# statuspanel.net
KiCad netlist of a schematic drawn in EAGLE
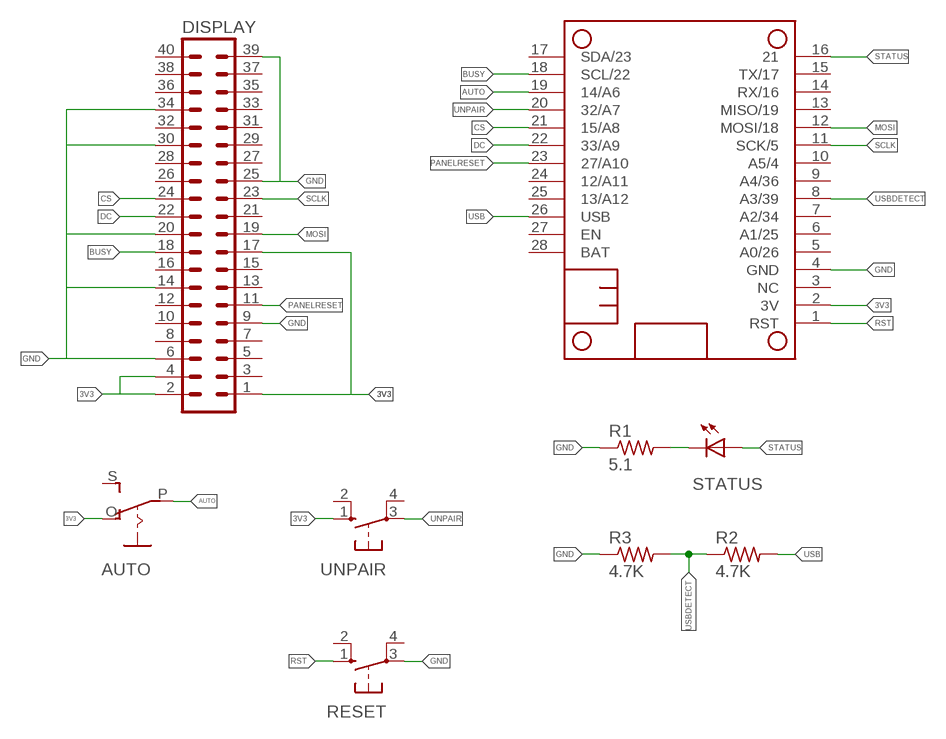
[diagram p0: schematic, sheet 1]

(export (version "E")
  (design (tool "Eeschema 10.0.6"))
  (components
    (comp (ref "AUTO")
      (value "EG1218S")
      (footprint "eagle-import:EG1218")
      (libsource (lib "eagle-import") (part "EG1218S"))
    )
    (comp (ref "DISPLAY")
      (value "MA20-2")
      (footprint "eagle-import:MA20-2")
      (libsource (lib "eagle-import") (part "MA20-2"))
    )
    (comp (ref "HUZZAH32")
      (value "HUZZAH32_NODIM")
      (footprint "eagle-import:FEATHERWING_DIM")
      (libsource (lib "eagle-import") (part "HUZZAH32_NODIM"))
    )
    (comp (ref "R1")
      (value "5.1")
      (footprint "eagle-import:R0805")
      (libsource (lib "eagle-import") (part "R-US_R0805"))
    )
    (comp (ref "R2")
      (value "4.7K")
      (footprint "eagle-import:R0805")
      (libsource (lib "eagle-import") (part "R-US_R0805"))
    )
    (comp (ref "R3")
      (value "4.7K")
      (footprint "eagle-import:R0805")
      (libsource (lib "eagle-import") (part "R-US_R0805"))
    )
    (comp (ref "RESET")
      (value "10-XX")
      (footprint "eagle-import:B3F-10XX")
      (fields (field (name "MPN") "B3F-1000"))
      (libsource (lib "eagle-import") (part "10-XX"))
    )
    (comp (ref "STATUS")
      (value "LED3MM")
      (footprint "eagle-import:LED3MM")
      (libsource (lib "eagle-import") (part "LED3MM"))
    )
    (comp (ref "UNPAIR")
      (value "10-XX")
      (footprint "eagle-import:B3F-10XX")
      (fields (field (name "MPN") "B3F-1000"))
      (libsource (lib "eagle-import") (part "10-XX"))
    )
  )
  (nets
    (net (code "1") (name "/BAT") (class "Default")
      (node (ref "HUZZAH32") (pin "28") (pinfunction "BAT_28") (pintype "power_in"))
    )
    (net (code "2") (name "3V3") (class "Default")
      (node (ref "AUTO") (pin "O") (pinfunction "O_O") (pintype "passive"))
      (node (ref "DISPLAY") (pin "1") (pinfunction "1_1") (pintype "passive"))
      (node (ref "DISPLAY") (pin "17") (pinfunction "17_17") (pintype "passive"))
      (node (ref "DISPLAY") (pin "2") (pinfunction "2_2") (pintype "passive"))
      (node (ref "DISPLAY") (pin "4") (pinfunction "4_4") (pintype "passive"))
      (node (ref "HUZZAH32") (pin "2") (pinfunction "3V_2") (pintype "power_in"))
      (node (ref "UNPAIR") (pin "1") (pinfunction "S_1") (pintype "passive"))
    )
    (net (code "3") (name "AUTO") (class "Default")
      (node (ref "AUTO") (pin "P") (pinfunction "P_P") (pintype "passive"))
      (node (ref "HUZZAH32") (pin "19") (pinfunction "14/A6_19") (pintype "bidirectional"))
    )
    (net (code "4") (name "BUSY") (class "Default")
      (node (ref "DISPLAY") (pin "18") (pinfunction "18_18") (pintype "passive"))
      (node (ref "HUZZAH32") (pin "18") (pinfunction "SCL/22_18") (pintype "bidirectional"))
    )
    (net (code "5") (name "CS") (class "Default")
      (node (ref "DISPLAY") (pin "24") (pinfunction "24_24") (pintype "passive"))
      (node (ref "HUZZAH32") (pin "21") (pinfunction "15/A8_21") (pintype "bidirectional"))
    )
    (net (code "6") (name "DC") (class "Default")
      (node (ref "DISPLAY") (pin "22") (pinfunction "22_22") (pintype "passive"))
      (node (ref "HUZZAH32") (pin "22") (pinfunction "33/A9_22") (pintype "bidirectional"))
    )
    (net (code "7") (name "GND") (class "Default")
      (node (ref "DISPLAY") (pin "14") (pinfunction "14_14") (pintype "passive"))
      (node (ref "DISPLAY") (pin "20") (pinfunction "20_20") (pintype "passive"))
      (node (ref "DISPLAY") (pin "25") (pinfunction "25_25") (pintype "passive"))
      (node (ref "DISPLAY") (pin "30") (pinfunction "30_30") (pintype "passive"))
      (node (ref "DISPLAY") (pin "34") (pinfunction "34_34") (pintype "passive"))
      (node (ref "DISPLAY") (pin "39") (pinfunction "39_39") (pintype "passive"))
      (node (ref "DISPLAY") (pin "6") (pinfunction "6_6") (pintype "passive"))
      (node (ref "DISPLAY") (pin "9") (pinfunction "9_9") (pintype "passive"))
      (node (ref "HUZZAH32") (pin "4") (pinfunction "GND_4") (pintype "power_in"))
      (node (ref "R1") (pin "1") (pinfunction "1_1") (pintype "passive"))
      (node (ref "R3") (pin "1") (pinfunction "1_1") (pintype "passive"))
      (node (ref "RESET") (pin "3") (pinfunction "P_3") (pintype "passive"))
    )
    (net (code "8") (name "MOSI") (class "Default")
      (node (ref "DISPLAY") (pin "19") (pinfunction "19_19") (pintype "passive"))
      (node (ref "HUZZAH32") (pin "12") (pinfunction "MOSI/18_12") (pintype "bidirectional"))
    )
    (net (code "9") (name "Net-(STATUS-C)") (class "Default")
      (node (ref "R1") (pin "2") (pinfunction "2_2") (pintype "passive"))
      (node (ref "STATUS") (pin "K") (pinfunction "C_K") (pintype "passive"))
    )
    (net (code "10") (name "PANELRESET") (class "Default")
      (node (ref "DISPLAY") (pin "11") (pinfunction "11_11") (pintype "passive"))
      (node (ref "HUZZAH32") (pin "23") (pinfunction "27/A10_23") (pintype "bidirectional"))
    )
    (net (code "11") (name "RST") (class "Default")
      (node (ref "HUZZAH32") (pin "1") (pinfunction "RST_1") (pintype "input"))
      (node (ref "RESET") (pin "1") (pinfunction "S_1") (pintype "passive"))
    )
    (net (code "12") (name "SCLK") (class "Default")
      (node (ref "DISPLAY") (pin "23") (pinfunction "23_23") (pintype "passive"))
      (node (ref "HUZZAH32") (pin "11") (pinfunction "SCK/5_11") (pintype "bidirectional"))
    )
    (net (code "13") (name "STATUS") (class "Default")
      (node (ref "HUZZAH32") (pin "16") (pinfunction "21_16") (pintype "bidirectional"))
      (node (ref "STATUS") (pin "A") (pinfunction "A_A") (pintype "passive"))
    )
    (net (code "14") (name "UNPAIR") (class "Default")
      (node (ref "HUZZAH32") (pin "20") (pinfunction "32/A7_20") (pintype "bidirectional"))
      (node (ref "UNPAIR") (pin "3") (pinfunction "P_3") (pintype "passive"))
    )
    (net (code "15") (name "USB") (class "Default")
      (node (ref "HUZZAH32") (pin "26") (pinfunction "USB_26") (pintype "power_in"))
      (node (ref "R2") (pin "2") (pinfunction "2_2") (pintype "passive"))
    )
    (net (code "16") (name "USBDETECT") (class "Default")
      (node (ref "HUZZAH32") (pin "8") (pinfunction "A3/39_8") (pintype "bidirectional"))
      (node (ref "R2") (pin "1") (pinfunction "1_1") (pintype "passive"))
      (node (ref "R3") (pin "2") (pinfunction "2_2") (pintype "passive"))
    )
    (net (code "17") (name "unconnected-(AUTO-PadS)") (class "Default")
      (node (ref "AUTO") (pin "S") (pinfunction "S_S") (pintype "passive"))
    )
    (net (code "18") (name "unconnected-(DISPLAY-Pad3)") (class "Default")
      (node (ref "DISPLAY") (pin "3") (pinfunction "3_3") (pintype "passive"))
    )
    (net (code "19") (name "unconnected-(DISPLAY-Pad5)") (class "Default")
      (node (ref "DISPLAY") (pin "5") (pinfunction "5_5") (pintype "passive"))
    )
    (net (code "20") (name "unconnected-(DISPLAY-Pad7)") (class "Default")
      (node (ref "DISPLAY") (pin "7") (pinfunction "7_7") (pintype "passive"))
    )
    (net (code "21") (name "unconnected-(DISPLAY-Pad8)") (class "Default")
      (node (ref "DISPLAY") (pin "8") (pinfunction "8_8") (pintype "passive"))
    )
    (net (code "22") (name "unconnected-(DISPLAY-Pad10)") (class "Default")
      (node (ref "DISPLAY") (pin "10") (pinfunction "10_10") (pintype "passive"))
    )
    (net (code "23") (name "unconnected-(DISPLAY-Pad12)") (class "Default")
      (node (ref "DISPLAY") (pin "12") (pinfunction "12_12") (pintype "passive"))
    )
    (net (code "24") (name "unconnected-(DISPLAY-Pad13)") (class "Default")
      (node (ref "DISPLAY") (pin "13") (pinfunction "13_13") (pintype "passive"))
    )
    (net (code "25") (name "unconnected-(DISPLAY-Pad15)") (class "Default")
      (node (ref "DISPLAY") (pin "15") (pinfunction "15_15") (pintype "passive"))
    )
    (net (code "26") (name "unconnected-(DISPLAY-Pad16)") (class "Default")
      (node (ref "DISPLAY") (pin "16") (pinfunction "16_16") (pintype "passive"))
    )
    (net (code "27") (name "unconnected-(DISPLAY-Pad21)") (class "Default")
      (node (ref "DISPLAY") (pin "21") (pinfunction "21_21") (pintype "passive"))
    )
    (net (code "28") (name "unconnected-(DISPLAY-Pad26)") (class "Default")
      (node (ref "DISPLAY") (pin "26") (pinfunction "26_26") (pintype "passive"))
    )
    (net (code "29") (name "unconnected-(DISPLAY-Pad27)") (class "Default")
      (node (ref "DISPLAY") (pin "27") (pinfunction "27_27") (pintype "passive"))
    )
    (net (code "30") (name "unconnected-(DISPLAY-Pad28)") (class "Default")
      (node (ref "DISPLAY") (pin "28") (pinfunction "28_28") (pintype "passive"))
    )
    (net (code "31") (name "unconnected-(DISPLAY-Pad29)") (class "Default")
      (node (ref "DISPLAY") (pin "29") (pinfunction "29_29") (pintype "passive"))
    )
    (net (code "32") (name "unconnected-(DISPLAY-Pad31)") (class "Default")
      (node (ref "DISPLAY") (pin "31") (pinfunction "31_31") (pintype "passive"))
    )
    (net (code "33") (name "unconnected-(DISPLAY-Pad32)") (class "Default")
      (node (ref "DISPLAY") (pin "32") (pinfunction "32_32") (pintype "passive"))
    )
    (net (code "34") (name "unconnected-(DISPLAY-Pad33)") (class "Default")
      (node (ref "DISPLAY") (pin "33") (pinfunction "33_33") (pintype "passive"))
    )
    (net (code "35") (name "unconnected-(DISPLAY-Pad35)") (class "Default")
      (node (ref "DISPLAY") (pin "35") (pinfunction "35_35") (pintype "passive"))
    )
    (net (code "36") (name "unconnected-(DISPLAY-Pad36)") (class "Default")
      (node (ref "DISPLAY") (pin "36") (pinfunction "36_36") (pintype "passive"))
    )
    (net (code "37") (name "unconnected-(DISPLAY-Pad37)") (class "Default")
      (node (ref "DISPLAY") (pin "37") (pinfunction "37_37") (pintype "passive"))
    )
    (net (code "38") (name "unconnected-(DISPLAY-Pad38)") (class "Default")
      (node (ref "DISPLAY") (pin "38") (pinfunction "38_38") (pintype "passive"))
    )
    (net (code "39") (name "unconnected-(DISPLAY-Pad40)") (class "Default")
      (node (ref "DISPLAY") (pin "40") (pinfunction "40_40") (pintype "passive"))
    )
    (net (code "40") (name "unconnected-(HUZZAH32-12{slash}A11-Pad24)") (class "Default")
      (node (ref "HUZZAH32") (pin "24") (pinfunction "12/A11_24") (pintype "bidirectional"))
    )
    (net (code "41") (name "unconnected-(HUZZAH32-13{slash}A12-Pad25)") (class "Default")
      (node (ref "HUZZAH32") (pin "25") (pinfunction "13/A12_25") (pintype "bidirectional"))
    )
    (net (code "42") (name "unconnected-(HUZZAH32-A0{slash}26-Pad5)") (class "Default")
      (node (ref "HUZZAH32") (pin "5") (pinfunction "A0/26_5") (pintype "bidirectional"))
    )
    (net (code "43") (name "unconnected-(HUZZAH32-A1{slash}25-Pad6)") (class "Default")
      (node (ref "HUZZAH32") (pin "6") (pinfunction "A1/25_6") (pintype "bidirectional"))
    )
    (net (code "44") (name "unconnected-(HUZZAH32-A2{slash}34-Pad7)") (class "Default")
      (node (ref "HUZZAH32") (pin "7") (pinfunction "A2/34_7") (pintype "bidirectional"))
    )
    (net (code "45") (name "unconnected-(HUZZAH32-A4{slash}36-Pad9)") (class "Default")
      (node (ref "HUZZAH32") (pin "9") (pinfunction "A4/36_9") (pintype "bidirectional"))
    )
    (net (code "46") (name "unconnected-(HUZZAH32-A5{slash}4-Pad10)") (class "Default")
      (node (ref "HUZZAH32") (pin "10") (pinfunction "A5/4_10") (pintype "bidirectional"))
    )
    (net (code "47") (name "unconnected-(HUZZAH32-EN-Pad27)") (class "Default")
      (node (ref "HUZZAH32") (pin "27") (pinfunction "EN_27") (pintype "passive"))
    )
    (net (code "48") (name "unconnected-(HUZZAH32-MISO{slash}19-Pad13)") (class "Default")
      (node (ref "HUZZAH32") (pin "13") (pinfunction "MISO/19_13") (pintype "bidirectional"))
    )
    (net (code "49") (name "unconnected-(HUZZAH32-NC-Pad3)") (class "Default")
      (node (ref "HUZZAH32") (pin "3") (pinfunction "NC_3") (pintype "passive"))
    )
    (net (code "50") (name "unconnected-(HUZZAH32-RX{slash}16-Pad14)") (class "Default")
      (node (ref "HUZZAH32") (pin "14") (pinfunction "RX/16_14") (pintype "bidirectional"))
    )
    (net (code "51") (name "unconnected-(HUZZAH32-SDA{slash}23-Pad17)") (class "Default")
      (node (ref "HUZZAH32") (pin "17") (pinfunction "SDA/23_17") (pintype "bidirectional"))
    )
    (net (code "52") (name "unconnected-(HUZZAH32-TX{slash}17-Pad15)") (class "Default")
      (node (ref "HUZZAH32") (pin "15") (pinfunction "TX/17_15") (pintype "bidirectional"))
    )
    (net (code "53") (name "unconnected-(RESET-P1-Pad4)") (class "Default")
      (node (ref "RESET") (pin "4") (pinfunction "P1_4") (pintype "passive"))
    )
    (net (code "54") (name "unconnected-(RESET-S1-Pad2)") (class "Default")
      (node (ref "RESET") (pin "2") (pinfunction "S1_2") (pintype "passive"))
    )
    (net (code "55") (name "unconnected-(UNPAIR-P1-Pad4)") (class "Default")
      (node (ref "UNPAIR") (pin "4") (pinfunction "P1_4") (pintype "passive"))
    )
    (net (code "56") (name "unconnected-(UNPAIR-S1-Pad2)") (class "Default")
      (node (ref "UNPAIR") (pin "2") (pinfunction "S1_2") (pintype "passive"))
    )
  )
)
